# AICat_V1_3.net
KiCad netlist of a schematic drawn in Altium Designer
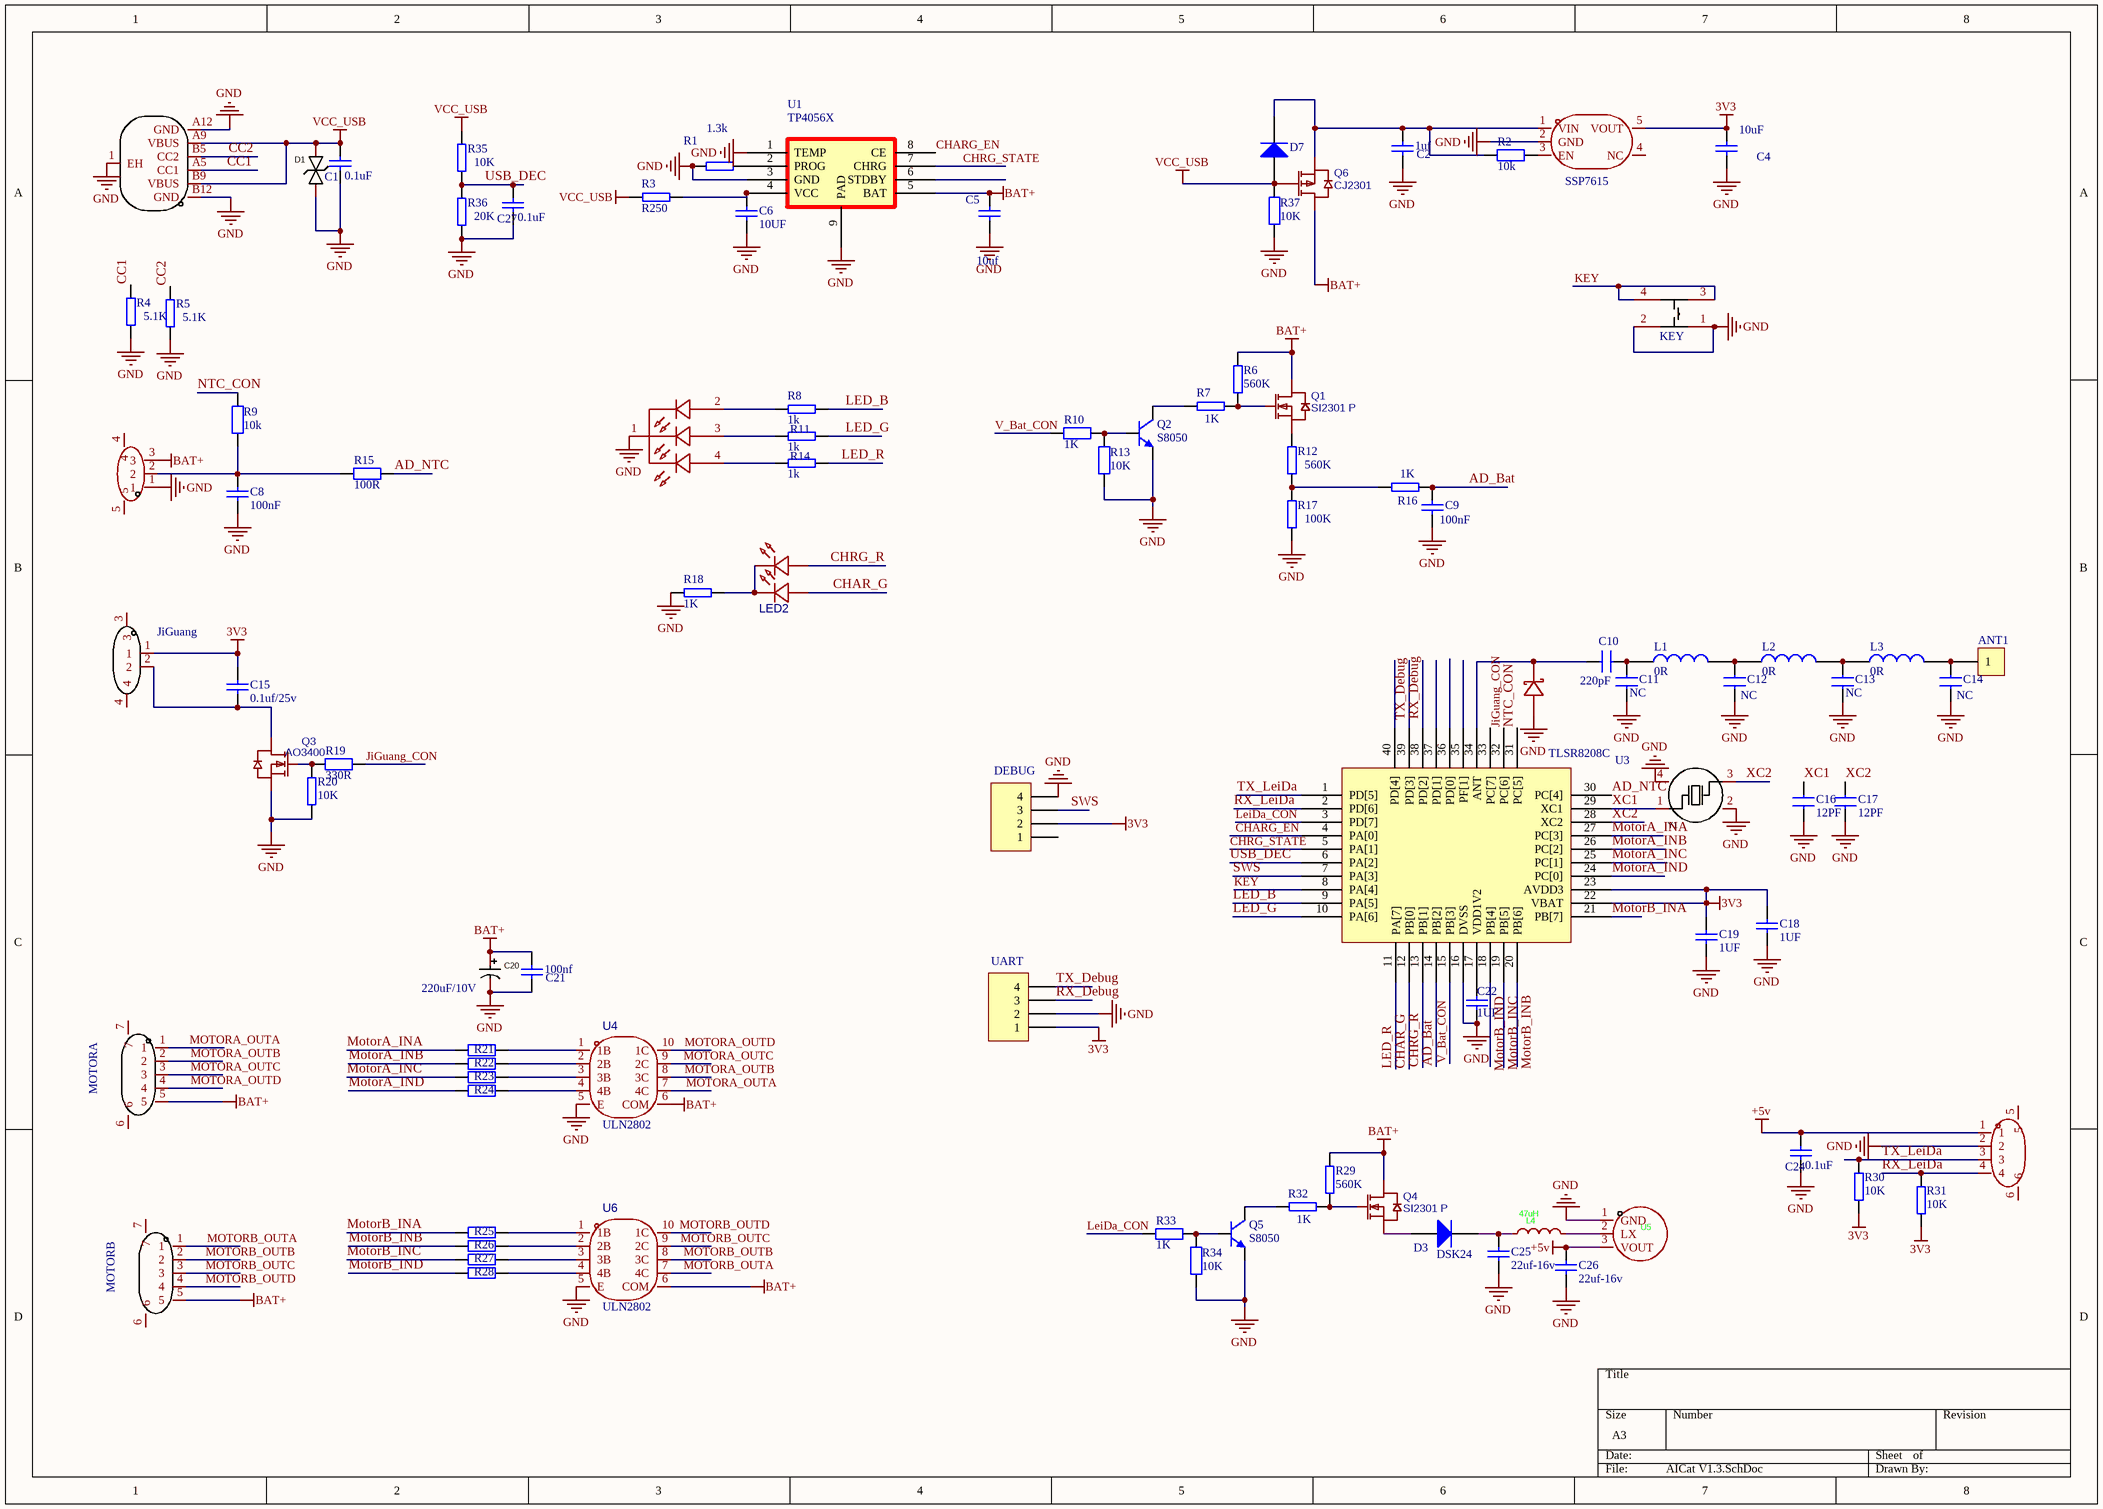
[diagram p0: AICat V1.3.SchDoc]

(export (version "E")
  (design (tool "Eeschema 10.0.6"))
  (components
    (comp (ref "ANT1")
      (value "~")
      (footprint "tp")
      (description "Connector")
      (libsource (lib "*") (part "CON1"))
    )
    (comp (ref "BAT1")
      (value "BX-PH2.0-3PWT")
      (footprint "HDR-TH_3P-P2.50_ZX-XH2.54-3PWZ")
      (libsource (lib "altium-import") (part "root_2_BX-PH2.0-3PWT_"))
    )
    (comp (ref "C1")
      (value "0.1uF")
      (footprint "0603_C")
      (description "Capacitor")
      (fields (field (name "PUBLISHER") "Altium Limited"))
      (libsource (lib "*") (part "Cap"))
    )
    (comp (ref "C2")
      (value "1uf")
      (footprint "0603_C")
      (description "无极电容")
      (libsource (lib "电容电阻电感保险") (part "Cap1"))
    )
    (comp (ref "C4")
      (value "10uF")
      (footprint "0603_C")
      (description "Capacitor")
      (fields (field (name "PUBLISHER") "Altium Limited"))
      (libsource (lib "*") (part "Cap"))
    )
    (comp (ref "C5")
      (value "10uf")
      (footprint "0603_C")
      (description "Capacitor")
      (fields (field (name "PUBLISHER") "Altium Limited"))
      (libsource (lib "*") (part "Cap"))
    )
    (comp (ref "C6") (value "10UF") (footprint "0603_c") (libsource (lib "DIY") (part "CAP")))
    (comp (ref "C8") (value "100nF") (footprint "0603_C") (libsource (lib "DIY") (part "CAP")))
    (comp (ref "C9") (value "100nF") (footprint "0603_C") (libsource (lib "DIY") (part "CAP")))
    (comp (ref "C10")
      (value "220pF")
      (footprint "0402_c")
      (description "Capacitor")
      (libsource (lib "*") (part "CAP"))
    )
    (comp (ref "C11")
      (value "NC")
      (footprint "0402_C")
      (description "Capacitor")
      (libsource (lib "*") (part "CAP"))
    )
    (comp (ref "C12")
      (value "NC")
      (footprint "0402_C")
      (description "Capacitor")
      (libsource (lib "*") (part "CAP"))
    )
    (comp (ref "C13")
      (value "NC")
      (footprint "0402_C")
      (description "Capacitor")
      (libsource (lib "*") (part "CAP"))
    )
    (comp (ref "C14")
      (value "NC")
      (footprint "0402_C")
      (description "Capacitor")
      (libsource (lib "*") (part "CAP"))
    )
    (comp (ref "C15")
      (value "0.1uf/25v")
      (footprint "0603_C")
      (description "Capacitor")
      (fields (field (name "PUBLISHER") "Altium Limited"))
      (libsource (lib "*") (part "Cap"))
    )
    (comp (ref "C16")
      (value "12PF")
      (footprint "0603_c")
      (description "Capacitor")
      (libsource (lib "*") (part "CAP"))
    )
    (comp (ref "C17")
      (value "12PF")
      (footprint "0603_c")
      (description "Capacitor")
      (libsource (lib "*") (part "CAP"))
    )
    (comp (ref "C18") (value "1UF") (footprint "0603_c") (libsource (lib "DIY") (part "CAP")))
    (comp (ref "C19") (value "1UF") (footprint "0603_c") (libsource (lib "DIY") (part "CAP")))
    (comp (ref "C20")
      (value "220uF/10V")
      (footprint "SMD 6.3*5.4 电解")
      (fields (field (name "MANUFACTURER PART") "RVT1A221M0605"))
      (libsource (lib "altium-import") (part "root_0_RVT1A221M0605_C72494_"))
    )
    (comp (ref "C21")
      (value "100nf")
      (footprint "0603_C")
      (description "无极电容")
      (libsource (lib "电容电阻电感保险") (part "Cap1"))
    )
    (comp (ref "C22") (value "1UF") (footprint "0603_c") (libsource (lib "DIY") (part "CAP")))
    (comp (ref "C24")
      (value "0.1uF")
      (footprint "0603_C")
      (description "Capacitor")
      (fields (field (name "PUBLISHER") "Altium Limited"))
      (libsource (lib "*") (part "Cap"))
    )
    (comp (ref "C25")
      (value "22uf-16v")
      (footprint "0805_c")
      (description "无极电容")
      (libsource (lib "电容电阻电感保险") (part "Cap1"))
    )
    (comp (ref "C26")
      (value "22uf-16v")
      (footprint "0805_c")
      (description "无极电容")
      (libsource (lib "电容电阻电感保险") (part "Cap1"))
    )
    (comp (ref "C27")
      (value "0.1uF")
      (footprint "0603_C")
      (description "Capacitor")
      (fields (field (name "PUBLISHER") "Altium Limited"))
      (libsource (lib "*") (part "Cap"))
    )
    (comp (ref "CN1")
      (value "JiGuang")
      (footprint "CONN-SMD_2P-P1.25-LT")
      (fields (field (name "MANUFACTURER PART") "HC-1.25-2PLT"))
      (libsource (lib "altium-import") (part "root_0_mirrored_HC-1.25-2PLT_"))
    )
    (comp (ref "CN2")
      (value "HC-1.25-4PLT")
      (footprint "CONN-SMD_4P-P1.25_LT")
      (libsource (lib "altium-import") (part "root_0_HC-1.25-4PLT_"))
    )
    (comp (ref "D1")
      (value "SMF5.0CA_C726939")
      (footprint "SOD-123 双向")
      (fields (field (name "MANUFACTURER PART") "SMF5.0CA"))
      (libsource (lib "altium-import") (part "root_1_SMF5.0CA_C726939_"))
    )
    (comp (ref "D2")
      (value "SE6V3LHN102T 6.3v单向")
      (footprint "0402-D")
      (libsource (lib "altium-import") (part "root_3_TPNSR05F20NXT5G_"))
    )
    (comp (ref "D3")
      (value "DSK24")
      (footprint "SOD-123FL")
      (description "High Conductance Fast Diode")
      (fields (field (name "PUBLISHER") "Altium Limited"))
      (libsource (lib "Miscellaneous Devices") (part "Diode 1N4148"))
    )
    (comp (ref "D7")
      (value "~")
      (footprint "SOD-123FL")
      (description "High Conductance Fast Diode")
      (fields (field (name "PUBLISHER") "Altium Limited"))
      (libsource (lib "Miscellaneous Devices") (part "Diode 1N4148"))
    )
    (comp (ref "J1")
      (value "MOTORA")
      (footprint "CONN-SMD_1.25-5PLT")
      (fields (field (name "MANUFACTURER PART") "HC-1.25-5PLT"))
      (libsource (lib "altium-import") (part "root_0_mirrored_HC-1.25-5PLT_"))
    )
    (comp (ref "J2")
      (value "MOTORB")
      (footprint "CONN-SMD_1.25-5PLT")
      (fields (field (name "MANUFACTURER PART") "HC-1.25-5PLT"))
      (libsource (lib "altium-import") (part "root_0_mirrored_HC-1.25-5PLT_"))
    )
    (comp (ref "K1")
      (value "KEY")
      (footprint "KEY_SMD_4P")
      (fields (field (name "MANUFACTURER PART") "TS-1002S-05026C"))
      (libsource (lib "altium-import") (part "root_2_TS-1002S-05026C_"))
    )
    (comp (ref "L1") (value "0R") (footprint "0402_R") (libsource (lib "*") (part "INDUCTOR")))
    (comp (ref "L2") (value "0R") (footprint "0402_R") (libsource (lib "*") (part "INDUCTOR")))
    (comp (ref "L3") (value "0R") (footprint "0402_R") (libsource (lib "*") (part "INDUCTOR")))
    (comp (ref "L4")
      (value "47uH")
      (footprint "IND-SMD_L3.5-W3.0_CD31")
      (fields (field (name "MANUFACTURER PART") "CD31-470M 47UH"))
      (libsource (lib "altium-import") (part "root_0_CD31-470M 47UH_"))
    )
    (comp (ref "LED1")
      (value "XL-A3528RGBC-BM")
      (footprint "LED-ARRAY-SMD_4P-L3.2-W2.8-LS3.5-BL_XL-A3528RGBC-BM")
      (libsource (lib "altium-import") (part "root_2_XL-A3528RGBC-BM_"))
    )
    (comp (ref "LED2")
      (value "*")
      (footprint "LED-SMD_4P-L3.2-W1.6-TL_XL-3216SURUGC")
      (libsource (lib "altium-import") (part "root_0_TJ-S2012SW8TCGLC2R2G-A5_"))
    )
    (comp (ref "P1")
      (value "DEBUG")
      (footprint "SIP4-2.54")
      (description "Header, 4-Pin")
      (fields (field (name "PUBLISHER") "Altium Limited"))
      (libsource (lib "Miscellaneous Connectors") (part "Header 4"))
    )
    (comp (ref "P2")
      (value "UART")
      (footprint "SIP4-2.54")
      (description "Header, 4-Pin")
      (fields (field (name "PUBLISHER") "Altium Limited"))
      (libsource (lib "Miscellaneous Connectors") (part "Header 4"))
    )
    (comp (ref "Q1")
      (value "SI2301 P")
      (footprint "SOT-23")
      (fields
        (field (name "BOM_SUPPLIER PART") "C2890442")
        (field (name "BOM_MANUFACTURER PART") "JMTL3400A")
        (field (name "CONTRIBUTOR") "LCSC")
      )
      (libsource (lib "altium-import") (part "root_0_JMTL3400A_"))
    )
    (comp (ref "Q2")
      (value "S8050")
      (footprint "SOT-23(SOT-23-3)")
      (description "NPN三极管")
      (libsource (lib "二三极管mos可控硅") (part "NPN_sot23"))
    )
    (comp (ref "Q3")
      (value "AO3400")
      (footprint "SOT-23")
      (fields
        (field (name "BOM_SUPPLIER PART") "C2890442")
        (field (name "BOM_MANUFACTURER PART") "JMTL3400A")
        (field (name "CONTRIBUTOR") "LCSC")
      )
      (libsource (lib "altium-import") (part "root_0_mirrored_JMTL3400A_"))
    )
    (comp (ref "Q4")
      (value "SI2301 P")
      (footprint "SOT-23")
      (fields
        (field (name "BOM_SUPPLIER PART") "C2890442")
        (field (name "BOM_MANUFACTURER PART") "JMTL3400A")
        (field (name "CONTRIBUTOR") "LCSC")
      )
      (libsource (lib "altium-import") (part "root_0_JMTL3400A_"))
    )
    (comp (ref "Q5")
      (value "S8050")
      (footprint "SOT-23(SOT-23-3)")
      (description "NPN三极管")
      (libsource (lib "二三极管mos可控硅") (part "NPN_sot23"))
    )
    (comp (ref "Q6")
      (value "CJ2301")
      (footprint "SOT-23")
      (fields (field (name "BOM_MANUFACTURER PART") "CJ3401") (field (name "BOM_SUPPLIER PART") "C13799"))
      (libsource (lib "altium-import") (part "root_2_mirrored_CJ3401_"))
    )
    (comp (ref "R1") (value "1.3k") (footprint "0603_R") (libsource (lib "DIY") (part "RES")))
    (comp (ref "R2")
      (value "10k")
      (footprint "0603_R")
      (description "Resistor")
      (fields (field (name "PUBLISHER") "Altium Limited"))
      (libsource (lib "") (part "Res2_3"))
    )
    (comp (ref "R3") (value "R250") (footprint "1206_R") (libsource (lib "DIY") (part "RES")))
    (comp (ref "R4") (value "5.1K") (footprint "0603_R") (libsource (lib "DIY") (part "RES")))
    (comp (ref "R5") (value "5.1K") (footprint "0603_R") (libsource (lib "DIY") (part "RES")))
    (comp (ref "R6") (value "560K") (footprint "0603_R") (libsource (lib "*") (part "RES")))
    (comp (ref "R7") (value "1K") (footprint "0603_R") (libsource (lib "") (part "RES_1")))
    (comp (ref "R8") (value "1k") (footprint "0603_R") (libsource (lib "DIY") (part "RES")))
    (comp (ref "R9")
      (value "10k")
      (footprint "0603_R")
      (description "Resistor")
      (fields (field (name "PUBLISHER") "Altium Limited"))
      (libsource (lib "*") (part "Res2"))
    )
    (comp (ref "R10")
      (value "1K")
      (footprint "0603_r")
      (description "Resistor")
      (fields (field (name "PUBLISHER") "Altium Limited"))
      (libsource (lib "") (part "Res2_2"))
    )
    (comp (ref "R11") (value "1k") (footprint "0603_R") (libsource (lib "DIY") (part "RES")))
    (comp (ref "R12") (value "560K") (footprint "0603_R") (libsource (lib "DIY") (part "RES")))
    (comp (ref "R13")
      (value "10K")
      (footprint "0603_r")
      (description "Resistor")
      (fields (field (name "PUBLISHER") "Altium Limited"))
      (libsource (lib "") (part "Res2_3"))
    )
    (comp (ref "R14") (value "1k") (footprint "0603_R") (libsource (lib "DIY") (part "RES")))
    (comp (ref "R15")
      (value "100R")
      (footprint "0603_R")
      (description "Resistor")
      (fields (field (name "PUBLISHER") "Altium Limited"))
      (libsource (lib "") (part "Res2_4"))
    )
    (comp (ref "R16") (value "1K") (footprint "0603_R") (libsource (lib "DIY") (part "RES")))
    (comp (ref "R17") (value "100K") (footprint "0603_R") (libsource (lib "DIY") (part "RES")))
    (comp (ref "R18") (value "1K") (footprint "0603_R") (libsource (lib "DIY") (part "RES")))
    (comp (ref "R19")
      (value "330R")
      (footprint "0603_R")
      (description "Resistor")
      (fields (field (name "PUBLISHER") "Altium Limited"))
      (libsource (lib "*") (part "Res2"))
    )
    (comp (ref "R20") (value "10K") (footprint "0603_R") (libsource (lib "DIY") (part "RES")))
    (comp (ref "R21")
      (value "330R")
      (footprint "0603_R")
      (description "Resistor")
      (fields (field (name "PUBLISHER") "Altium Limited"))
      (libsource (lib "") (part "Res2_1"))
    )
    (comp (ref "R22")
      (value "330R")
      (footprint "0603_R")
      (description "Resistor")
      (fields (field (name "PUBLISHER") "Altium Limited"))
      (libsource (lib "") (part "Res2_1"))
    )
    (comp (ref "R23")
      (value "330R")
      (footprint "0603_R")
      (description "Resistor")
      (fields (field (name "PUBLISHER") "Altium Limited"))
      (libsource (lib "") (part "Res2_1"))
    )
    (comp (ref "R24")
      (value "330R")
      (footprint "0603_R")
      (description "Resistor")
      (fields (field (name "PUBLISHER") "Altium Limited"))
      (libsource (lib "") (part "Res2_1"))
    )
    (comp (ref "R25")
      (value "330R")
      (footprint "0603_R")
      (description "Resistor")
      (fields (field (name "PUBLISHER") "Altium Limited"))
      (libsource (lib "") (part "Res2_1"))
    )
    (comp (ref "R26")
      (value "330R")
      (footprint "0603_R")
      (description "Resistor")
      (fields (field (name "PUBLISHER") "Altium Limited"))
      (libsource (lib "") (part "Res2_1"))
    )
    (comp (ref "R27")
      (value "330R")
      (footprint "0603_R")
      (description "Resistor")
      (fields (field (name "PUBLISHER") "Altium Limited"))
      (libsource (lib "") (part "Res2_1"))
    )
    (comp (ref "R28")
      (value "330R")
      (footprint "0603_R")
      (description "Resistor")
      (fields (field (name "PUBLISHER") "Altium Limited"))
      (libsource (lib "") (part "Res2_1"))
    )
    (comp (ref "R29") (value "560K") (footprint "0603_R") (libsource (lib "*") (part "RES")))
    (comp (ref "R30") (value "10K") (footprint "0603_R") (libsource (lib "*") (part "RES")))
    (comp (ref "R31") (value "10K") (footprint "0603_R") (libsource (lib "*") (part "RES")))
    (comp (ref "R32") (value "1K") (footprint "0603_R") (libsource (lib "") (part "RES_1")))
    (comp (ref "R33")
      (value "1K")
      (footprint "0603_r")
      (description "Resistor")
      (fields (field (name "PUBLISHER") "Altium Limited"))
      (libsource (lib "") (part "Res2_2"))
    )
    (comp (ref "R34")
      (value "10K")
      (footprint "0603_r")
      (description "Resistor")
      (fields (field (name "PUBLISHER") "Altium Limited"))
      (libsource (lib "") (part "Res2_3"))
    )
    (comp (ref "R35") (value "10K") (footprint "0603_R") (libsource (lib "DIY") (part "RES")))
    (comp (ref "R36") (value "20K") (footprint "0603_R") (libsource (lib "DIY") (part "RES")))
    (comp (ref "R37")
      (value "10K")
      (footprint "0603_R")
      (description "Resistor")
      (fields (field (name "PUBLISHER") "Altium Limited"))
      (libsource (lib "*") (part "Res2"))
    )
    (comp (ref "U1")
      (value "TP4056X")
      (footprint "SOP8-9")
      (description "TP4056")
      (libsource (lib "芯片") (part "TP4056"))
    )
    (comp (ref "U2")
      (value "SSP7615")
      (footprint "SOT-23-5")
      (libsource (lib "altium-import") (part "root_0_SSP7615-33M5R_"))
    )
    (comp (ref "U3")
      (value "TLSR8208C")
      (footprint "QFN-40_L5.0-W5.0-P0.40-BL-EP3.7")
      (libsource (lib "MyLib") (part "TLSR8208C"))
    )
    (comp (ref "U4")
      (value "ULN2802")
      (footprint "ESSOP-10")
      (libsource (lib "altium-import") (part "root_0_ULN2802_C2828555_"))
    )
    (comp (ref "U5")
      (value "HE9116A50NR")
      (footprint "SOT-23")
      (libsource (lib "altium-import") (part "root_0_HE9116A50NR_"))
    )
    (comp (ref "U6")
      (value "ULN2802")
      (footprint "ESSOP-10")
      (libsource (lib "altium-import") (part "root_0_ULN2802_C2828555_"))
    )
    (comp (ref "USB1")
      (value "TYPE-C 6P")
      (footprint "TPYE-C-6")
      (fields (field (name "MANUFACTURER PART") "TYPE-C 6P LTH6.5"))
      (libsource (lib "altium-import") (part "root_2_TYPE-C 6P LTH6.5_"))
    )
    (comp (ref "Y1")
      (value "24MHz +-20PPM")
      (footprint "CRYSTAL-SMD_4P-L3.2-W2.5")
      (fields (field (name "MANUFACTURER PART") "TAXM13.56M4RLBCCT2T"))
      (libsource (lib "altium-import") (part "root_0_TAXM13.56M4RLBCCT2T_"))
    )
  )
  (nets
    (net (code "1") (name "+5v") (class "Default")
      (node (ref "C24") (pin "2") (pinfunction "2_2") (pintype "passive"))
      (node (ref "C26") (pin "1") (pinfunction "1_1") (pintype "passive"))
      (node (ref "CN2") (pin "1") (pinfunction "1_1") (pintype "passive"))
      (node (ref "U5") (pin "3") (pinfunction "VOUT_3") (pintype "passive"))
    )
    (net (code "2") (name "/AD_Bat") (class "Default")
      (node (ref "C9") (pin "2") (pintype "passive"))
      (node (ref "R16") (pin "1") (pinfunction "1_1") (pintype "passive"))
      (node (ref "U3") (pin "14") (pinfunction "PB[2]_14") (pintype "passive"))
    )
    (net (code "3") (name "/AD_NTC") (class "Default")
      (node (ref "R15") (pin "1") (pinfunction "1_1") (pintype "passive"))
      (node (ref "U3") (pin "30") (pinfunction "PC[4]_30") (pintype "passive"))
    )
    (net (code "4") (name "/CC1") (class "Default")
      (node (ref "R4") (pin "1") (pinfunction "1_1") (pintype "passive"))
      (node (ref "USB1") (pin "A5") (pinfunction "CC1_A5") (pintype "passive"))
    )
    (net (code "5") (name "/CC2") (class "Default")
      (node (ref "R5") (pin "1") (pinfunction "1_1") (pintype "passive"))
      (node (ref "USB1") (pin "B5") (pinfunction "CC2_B5") (pintype "passive"))
    )
    (net (code "6") (name "/CHARG_EN") (class "Default")
      (node (ref "U1") (pin "8") (pinfunction "CE_8") (pintype "passive"))
      (node (ref "U3") (pin "4") (pinfunction "PA[0]_4") (pintype "passive"))
    )
    (net (code "7") (name "/CHAR_G") (class "Default")
      (node (ref "LED2") (pin "3") (pinfunction "A_3") (pintype "passive"))
      (node (ref "U3") (pin "12") (pinfunction "PB[0]_12") (pintype "passive"))
    )
    (net (code "8") (name "/CHRG_R") (class "Default")
      (node (ref "LED2") (pin "1") (pinfunction "A_1") (pintype "passive"))
      (node (ref "U3") (pin "13") (pinfunction "PB[1]_13") (pintype "passive"))
    )
    (net (code "9") (name "/CHRG_STATE") (class "Default")
      (node (ref "U1") (pin "7") (pinfunction "CHRG_7") (pintype "passive"))
      (node (ref "U3") (pin "5") (pinfunction "PA[1]_5") (pintype "passive"))
    )
    (net (code "10") (name "/JiGuang_CON") (class "Default")
      (node (ref "R19") (pin "2") (pinfunction "2_2") (pintype "passive"))
      (node (ref "U3") (pin "32") (pinfunction "PC[6]_32") (pintype "passive"))
    )
    (net (code "11") (name "/KEY") (class "Default")
      (node (ref "K1") (pin "3") (pinfunction "3_3") (pintype "passive"))
      (node (ref "K1") (pin "4") (pinfunction "4_4") (pintype "passive"))
      (node (ref "U3") (pin "8") (pinfunction "PA[4]_8") (pintype "passive"))
    )
    (net (code "12") (name "/LED_B") (class "Default")
      (node (ref "R8") (pin "2") (pinfunction "2_2") (pintype "passive"))
      (node (ref "U3") (pin "9") (pinfunction "PA[5]_9") (pintype "passive"))
    )
    (net (code "13") (name "/LED_G") (class "Default")
      (node (ref "R11") (pin "2") (pinfunction "2_2") (pintype "passive"))
      (node (ref "U3") (pin "10") (pinfunction "PA[6]_10") (pintype "passive"))
    )
    (net (code "14") (name "/LED_R") (class "Default")
      (node (ref "R14") (pin "2") (pinfunction "2_2") (pintype "passive"))
      (node (ref "U3") (pin "11") (pinfunction "PA[7]_11") (pintype "passive"))
    )
    (net (code "15") (name "/LeiDa_CON") (class "Default")
      (node (ref "R33") (pin "2") (pinfunction "2_2") (pintype "passive"))
      (node (ref "U3") (pin "3") (pinfunction "PD[7]_3") (pintype "passive"))
    )
    (net (code "16") (name "/MOTORA_OUTA") (class "Default")
      (node (ref "J1") (pin "1") (pinfunction "1_1") (pintype "passive"))
      (node (ref "U4") (pin "7") (pinfunction "4C_7") (pintype "passive"))
    )
    (net (code "17") (name "/MOTORA_OUTB") (class "Default")
      (node (ref "J1") (pin "2") (pinfunction "2_2") (pintype "passive"))
      (node (ref "U4") (pin "8") (pinfunction "3C_8") (pintype "passive"))
    )
    (net (code "18") (name "/MOTORA_OUTC") (class "Default")
      (node (ref "J1") (pin "3") (pinfunction "3_3") (pintype "passive"))
      (node (ref "U4") (pin "9") (pinfunction "2C_9") (pintype "passive"))
    )
    (net (code "19") (name "/MOTORA_OUTD") (class "Default")
      (node (ref "J1") (pin "4") (pinfunction "4_4") (pintype "passive"))
      (node (ref "U4") (pin "10") (pinfunction "1C_10") (pintype "passive"))
    )
    (net (code "20") (name "/MOTORB_OUTA") (class "Default")
      (node (ref "J2") (pin "1") (pinfunction "1_1") (pintype "passive"))
      (node (ref "U6") (pin "7") (pinfunction "4C_7") (pintype "passive"))
    )
    (net (code "21") (name "/MOTORB_OUTB") (class "Default")
      (node (ref "J2") (pin "2") (pinfunction "2_2") (pintype "passive"))
      (node (ref "U6") (pin "8") (pinfunction "3C_8") (pintype "passive"))
    )
    (net (code "22") (name "/MOTORB_OUTC") (class "Default")
      (node (ref "J2") (pin "3") (pinfunction "3_3") (pintype "passive"))
      (node (ref "U6") (pin "9") (pinfunction "2C_9") (pintype "passive"))
    )
    (net (code "23") (name "/MOTORB_OUTD") (class "Default")
      (node (ref "J2") (pin "4") (pinfunction "4_4") (pintype "passive"))
      (node (ref "U6") (pin "10") (pinfunction "1C_10") (pintype "passive"))
    )
    (net (code "24") (name "/MotorA_INA") (class "Default")
      (node (ref "R21") (pin "2") (pinfunction "2_2") (pintype "passive"))
      (node (ref "U3") (pin "27") (pinfunction "PC[3]_27") (pintype "passive"))
    )
    (net (code "25") (name "/MotorA_INB") (class "Default")
      (node (ref "R22") (pin "2") (pinfunction "2_2") (pintype "passive"))
      (node (ref "U3") (pin "26") (pinfunction "PC[2]_26") (pintype "passive"))
    )
    (net (code "26") (name "/MotorA_INC") (class "Default")
      (node (ref "R23") (pin "2") (pinfunction "2_2") (pintype "passive"))
      (node (ref "U3") (pin "25") (pinfunction "PC[1]_25") (pintype "passive"))
    )
    (net (code "27") (name "/MotorA_IND") (class "Default")
      (node (ref "R24") (pin "2") (pinfunction "2_2") (pintype "passive"))
      (node (ref "U3") (pin "24") (pinfunction "PC[0]_24") (pintype "passive"))
    )
    (net (code "28") (name "/MotorB_INA") (class "Default")
      (node (ref "R25") (pin "2") (pinfunction "2_2") (pintype "passive"))
      (node (ref "U3") (pin "21") (pinfunction "PB[7]_21") (pintype "passive"))
    )
    (net (code "29") (name "/MotorB_INB") (class "Default")
      (node (ref "R26") (pin "2") (pinfunction "2_2") (pintype "passive"))
      (node (ref "U3") (pin "20") (pinfunction "PB[6]_20") (pintype "passive"))
    )
    (net (code "30") (name "/MotorB_INC") (class "Default")
      (node (ref "R27") (pin "2") (pinfunction "2_2") (pintype "passive"))
      (node (ref "U3") (pin "19") (pinfunction "PB[5]_19") (pintype "passive"))
    )
    (net (code "31") (name "/MotorB_IND") (class "Default")
      (node (ref "R28") (pin "2") (pinfunction "2_2") (pintype "passive"))
      (node (ref "U3") (pin "18") (pinfunction "PB[4]_18") (pintype "passive"))
    )
    (net (code "32") (name "/NTC_CON") (class "Default")
      (node (ref "R9") (pin "2") (pinfunction "2_2") (pintype "passive"))
      (node (ref "U3") (pin "31") (pinfunction "PC[5]_31") (pintype "passive"))
    )
    (net (code "33") (name "/RX_Debug") (class "Default")
      (node (ref "P2") (pin "3") (pinfunction "3_3") (pintype "passive"))
      (node (ref "U3") (pin "38") (pinfunction "PD[2]_38") (pintype "passive"))
    )
    (net (code "34") (name "/RX_LeiDa") (class "Default")
      (node (ref "CN2") (pin "4") (pinfunction "4_4") (pintype "passive"))
      (node (ref "R31") (pin "1") (pintype "passive"))
      (node (ref "U3") (pin "2") (pinfunction "PD[6]_2") (pintype "passive"))
    )
    (net (code "35") (name "/SWS") (class "Default")
      (node (ref "P1") (pin "3") (pinfunction "3_3") (pintype "passive"))
      (node (ref "U3") (pin "7") (pinfunction "PA[3]_7") (pintype "passive"))
    )
    (net (code "36") (name "/TX_Debug") (class "Default")
      (node (ref "P2") (pin "4") (pinfunction "4_4") (pintype "passive"))
      (node (ref "U3") (pin "39") (pinfunction "PD[3]_39") (pintype "passive"))
    )
    (net (code "37") (name "/TX_LeiDa") (class "Default")
      (node (ref "CN2") (pin "3") (pinfunction "3_3") (pintype "passive"))
      (node (ref "R30") (pin "1") (pintype "passive"))
      (node (ref "U3") (pin "1") (pinfunction "PD[5]_1") (pintype "passive"))
    )
    (net (code "38") (name "/USB_DEC") (class "Default")
      (node (ref "C27") (pin "2") (pinfunction "2_2") (pintype "passive"))
      (node (ref "R35") (pin "2") (pinfunction "2_2") (pintype "passive"))
      (node (ref "R36") (pin "1") (pinfunction "1_1") (pintype "passive"))
      (node (ref "U3") (pin "6") (pinfunction "PA[2]_6") (pintype "passive"))
    )
    (net (code "39") (name "/V_Bat_CON") (class "Default")
      (node (ref "R10") (pin "2") (pinfunction "2_2") (pintype "passive"))
      (node (ref "U3") (pin "15") (pinfunction "PB[3]_15") (pintype "passive"))
    )
    (net (code "40") (name "/XC1") (class "Default")
      (node (ref "C16") (pin "2") (pinfunction "2_2") (pintype "passive"))
      (node (ref "U3") (pin "29") (pinfunction "XC1_29") (pintype "passive"))
      (node (ref "Y1") (pin "1") (pinfunction "OSC1_1") (pintype "passive"))
    )
    (net (code "41") (name "/XC2") (class "Default")
      (node (ref "C17") (pin "2") (pinfunction "2_2") (pintype "passive"))
      (node (ref "U3") (pin "28") (pinfunction "XC2_28") (pintype "passive"))
      (node (ref "Y1") (pin "3") (pinfunction "OSC2_3") (pintype "passive"))
    )
    (net (code "42") (name "3V3") (class "Default")
      (node (ref "C15") (pin "2") (pinfunction "2_2") (pintype "passive"))
      (node (ref "C18") (pin "1") (pintype "passive"))
      (node (ref "C19") (pin "1") (pintype "passive"))
      (node (ref "C4") (pin "2") (pinfunction "2_2") (pintype "passive"))
      (node (ref "CN1") (pin "1") (pinfunction "1_1") (pintype "passive"))
      (node (ref "P1") (pin "2") (pinfunction "2_2") (pintype "passive"))
      (node (ref "P2") (pin "1") (pinfunction "1_1") (pintype "passive"))
      (node (ref "R30") (pin "2") (pintype "passive"))
      (node (ref "R31") (pin "2") (pintype "passive"))
      (node (ref "U2") (pin "5") (pinfunction "VOUT_5") (pintype "passive"))
      (node (ref "U3") (pin "22") (pinfunction "VBAT_22") (pintype "passive"))
      (node (ref "U3") (pin "23") (pinfunction "AVDD3_23") (pintype "passive"))
    )
    (net (code "43") (name "BAT+") (class "Default")
      (node (ref "BAT1") (pin "3") (pinfunction "3_3") (pintype "passive"))
      (node (ref "C20") (pin "1") (pinfunction "1_1") (pintype "passive"))
      (node (ref "C21") (pin "2") (pinfunction "2_2") (pintype "passive"))
      (node (ref "C5") (pin "1") (pinfunction "1_1") (pintype "passive"))
      (node (ref "J1") (pin "5") (pinfunction "5_5") (pintype "passive"))
      (node (ref "J2") (pin "5") (pinfunction "5_5") (pintype "passive"))
      (node (ref "Q1") (pin "2") (pinfunction "D_2") (pintype "passive"))
      (node (ref "Q4") (pin "2") (pinfunction "D_2") (pintype "passive"))
      (node (ref "Q6") (pin "3") (pinfunction "D_3") (pintype "passive"))
      (node (ref "R29") (pin "1") (pintype "passive"))
      (node (ref "R6") (pin "1") (pintype "passive"))
      (node (ref "U1") (pin "5") (pinfunction "BAT_5") (pintype "passive"))
      (node (ref "U4") (pin "6") (pinfunction "COM_6") (pintype "passive"))
      (node (ref "U6") (pin "6") (pinfunction "COM_6") (pintype "passive"))
    )
    (net (code "44") (name "GND") (class "Default")
      (node (ref "BAT1") (pin "1") (pinfunction "1_1") (pintype "passive"))
      (node (ref "C1") (pin "1") (pinfunction "1_1") (pintype "passive"))
      (node (ref "C11") (pin "1") (pinfunction "1_1") (pintype "passive"))
      (node (ref "C12") (pin "1") (pinfunction "1_1") (pintype "passive"))
      (node (ref "C13") (pin "1") (pinfunction "1_1") (pintype "passive"))
      (node (ref "C14") (pin "1") (pinfunction "1_1") (pintype "passive"))
      (node (ref "C16") (pin "1") (pinfunction "1_1") (pintype "passive"))
      (node (ref "C17") (pin "1") (pinfunction "1_1") (pintype "passive"))
      (node (ref "C18") (pin "2") (pintype "passive"))
      (node (ref "C19") (pin "2") (pintype "passive"))
      (node (ref "C2") (pin "1") (pinfunction "1_1") (pintype "passive"))
      (node (ref "C20") (pin "2") (pinfunction "2_2") (pintype "passive"))
      (node (ref "C21") (pin "1") (pinfunction "1_1") (pintype "passive"))
      (node (ref "C22") (pin "1") (pintype "passive"))
      (node (ref "C24") (pin "1") (pinfunction "1_1") (pintype "passive"))
      (node (ref "C25") (pin "2") (pinfunction "2_2") (pintype "passive"))
      (node (ref "C26") (pin "2") (pinfunction "2_2") (pintype "passive"))
      (node (ref "C27") (pin "1") (pinfunction "1_1") (pintype "passive"))
      (node (ref "C4") (pin "1") (pinfunction "1_1") (pintype "passive"))
      (node (ref "C5") (pin "2") (pinfunction "2_2") (pintype "passive"))
      (node (ref "C6") (pin "1") (pintype "passive"))
      (node (ref "C8") (pin "2") (pintype "passive"))
      (node (ref "C9") (pin "1") (pintype "passive"))
      (node (ref "CN2") (pin "2") (pinfunction "2_2") (pintype "passive"))
      (node (ref "D1") (pin "1") (pinfunction "1_1") (pintype "passive"))
      (node (ref "D2") (pin "2") (pinfunction "A_2") (pintype "passive"))
      (node (ref "K1") (pin "1") (pinfunction "1_1") (pintype "passive"))
      (node (ref "K1") (pin "2") (pinfunction "2_2") (pintype "passive"))
      (node (ref "LED1") (pin "1") (pinfunction "1_1") (pintype "passive"))
      (node (ref "P1") (pin "4") (pinfunction "4_4") (pintype "passive"))
      (node (ref "P2") (pin "2") (pinfunction "2_2") (pintype "passive"))
      (node (ref "Q2") (pin "2") (pinfunction "E_2") (pintype "passive"))
      (node (ref "Q3") (pin "2") (pinfunction "S_2") (pintype "passive"))
      (node (ref "Q5") (pin "2") (pinfunction "E_2") (pintype "passive"))
      (node (ref "R1") (pin "1") (pinfunction "1_1") (pintype "passive"))
      (node (ref "R13") (pin "1") (pinfunction "1_1") (pintype "passive"))
      (node (ref "R17") (pin "2") (pinfunction "2_2") (pintype "passive"))
      (node (ref "R18") (pin "1") (pinfunction "1_1") (pintype "passive"))
      (node (ref "R20") (pin "1") (pinfunction "1_1") (pintype "passive"))
      (node (ref "R34") (pin "1") (pinfunction "1_1") (pintype "passive"))
      (node (ref "R36") (pin "2") (pinfunction "2_2") (pintype "passive"))
      (node (ref "R37") (pin "1") (pinfunction "1_1") (pintype "passive"))
      (node (ref "R4") (pin "2") (pinfunction "2_2") (pintype "passive"))
      (node (ref "R5") (pin "2") (pinfunction "2_2") (pintype "passive"))
      (node (ref "U1") (pin "1") (pinfunction "TEMP_1") (pintype "passive"))
      (node (ref "U1") (pin "3") (pinfunction "GND_3") (pintype "passive"))
      (node (ref "U1") (pin "9") (pinfunction "PAD_9") (pintype "passive"))
      (node (ref "U2") (pin "2") (pinfunction "GND_2") (pintype "passive"))
      (node (ref "U3") (pin "16") (pinfunction "DVSS_16") (pintype "passive"))
      (node (ref "U4") (pin "5") (pinfunction "E_5") (pintype "passive"))
      (node (ref "U5") (pin "1") (pinfunction "GND_1") (pintype "passive"))
      (node (ref "U6") (pin "5") (pinfunction "E_5") (pintype "passive"))
      (node (ref "USB1") (pin "1") (pinfunction "EH_1") (pintype "passive"))
      (node (ref "USB1") (pin "A12") (pinfunction "GND_A12") (pintype "passive"))
      (node (ref "USB1") (pin "B12") (pinfunction "GND_B12") (pintype "passive"))
      (node (ref "Y1") (pin "2") (pinfunction "GND_2") (pintype "passive"))
      (node (ref "Y1") (pin "4") (pinfunction "GND_4") (pintype "passive"))
    )
    (net (code "45") (name "Net-(ANT1-Pad1)") (class "Default")
      (node (ref "ANT1") (pin "1") (pinfunction "1_1") (pintype "passive"))
      (node (ref "C14") (pin "2") (pinfunction "2_2") (pintype "passive"))
      (node (ref "L3") (pin "2") (pinfunction "2_2") (pintype "passive"))
    )
    (net (code "46") (name "Net-(BAT1-Pad2)") (class "Default")
      (node (ref "BAT1") (pin "2") (pinfunction "2_2") (pintype "passive"))
      (node (ref "C8") (pin "1") (pintype "passive"))
      (node (ref "R15") (pin "2") (pinfunction "2_2") (pintype "passive"))
      (node (ref "R9") (pin "1") (pinfunction "1_1") (pintype "passive"))
    )
    (net (code "47") (name "Net-(C10-Pad2)") (class "Default")
      (node (ref "C10") (pin "2") (pinfunction "2_2") (pintype "passive"))
      (node (ref "C11") (pin "2") (pinfunction "2_2") (pintype "passive"))
      (node (ref "L1") (pin "1") (pinfunction "1_1") (pintype "passive"))
    )
    (net (code "48") (name "Net-(C12-Pad2)") (class "Default")
      (node (ref "C12") (pin "2") (pinfunction "2_2") (pintype "passive"))
      (node (ref "L1") (pin "2") (pinfunction "2_2") (pintype "passive"))
      (node (ref "L2") (pin "1") (pinfunction "1_1") (pintype "passive"))
    )
    (net (code "49") (name "Net-(C13-Pad2)") (class "Default")
      (node (ref "C13") (pin "2") (pinfunction "2_2") (pintype "passive"))
      (node (ref "L2") (pin "2") (pinfunction "2_2") (pintype "passive"))
      (node (ref "L3") (pin "1") (pinfunction "1_1") (pintype "passive"))
    )
    (net (code "50") (name "Net-(D2-C)") (class "Default")
      (node (ref "C10") (pin "1") (pinfunction "1_1") (pintype "passive"))
      (node (ref "D2") (pin "1") (pinfunction "C_1") (pintype "passive"))
      (node (ref "U3") (pin "34") (pinfunction "ANT_34") (pintype "passive"))
    )
    (net (code "51") (name "Net-(D3-A)") (class "Default")
      (node (ref "D3") (pin "1") (pinfunction "A_1") (pintype "passive"))
      (node (ref "Q4") (pin "3") (pinfunction "S_3") (pintype "passive"))
    )
    (net (code "52") (name "Net-(D3-K)") (class "Default")
      (node (ref "C25") (pin "1") (pinfunction "1_1") (pintype "passive"))
      (node (ref "D3") (pin "2") (pinfunction "K_2") (pintype "passive"))
      (node (ref "L4") (pin "1") (pinfunction "1_1") (pintype "passive"))
    )
    (net (code "53") (name "Net-(D7-K)") (class "Default")
      (node (ref "C2") (pin "2") (pinfunction "2_2") (pintype "passive"))
      (node (ref "D7") (pin "2") (pinfunction "K_2") (pintype "passive"))
      (node (ref "Q6") (pin "2") (pinfunction "S_2") (pintype "passive"))
      (node (ref "R2") (pin "1") (pinfunction "1_1") (pintype "passive"))
      (node (ref "U2") (pin "1") (pinfunction "VIN_1") (pintype "passive"))
    )
    (net (code "54") (name "Net-(LED1-Pad2)") (class "Default")
      (node (ref "LED1") (pin "2") (pinfunction "2_2") (pintype "passive"))
      (node (ref "R8") (pin "1") (pinfunction "1_1") (pintype "passive"))
    )
    (net (code "55") (name "Net-(LED1-Pad3)") (class "Default")
      (node (ref "LED1") (pin "3") (pinfunction "3_3") (pintype "passive"))
      (node (ref "R11") (pin "1") (pinfunction "1_1") (pintype "passive"))
    )
    (net (code "56") (name "Net-(LED1-Pad4)") (class "Default")
      (node (ref "LED1") (pin "4") (pinfunction "4_4") (pintype "passive"))
      (node (ref "R14") (pin "1") (pinfunction "1_1") (pintype "passive"))
    )
    (net (code "57") (name "Net-(LED2-K-Pad2)") (class "Default")
      (node (ref "LED2") (pin "2") (pinfunction "K_2") (pintype "passive"))
      (node (ref "LED2") (pin "4") (pinfunction "K_4") (pintype "passive"))
      (node (ref "R18") (pin "2") (pinfunction "2_2") (pintype "passive"))
    )
    (net (code "58") (name "Net-(Q1-G)") (class "Default")
      (node (ref "Q1") (pin "1") (pinfunction "G_1") (pintype "passive"))
      (node (ref "R6") (pin "2") (pintype "passive"))
      (node (ref "R7") (pin "1") (pintype "passive"))
    )
    (net (code "59") (name "Net-(Q1-S)") (class "Default")
      (node (ref "Q1") (pin "3") (pinfunction "S_3") (pintype "passive"))
      (node (ref "R12") (pin "1") (pinfunction "1_1") (pintype "passive"))
    )
    (net (code "60") (name "Net-(Q2-B)") (class "Default")
      (node (ref "Q2") (pin "1") (pinfunction "B_1") (pintype "passive"))
      (node (ref "R10") (pin "1") (pinfunction "1_1") (pintype "passive"))
      (node (ref "R13") (pin "2") (pinfunction "2_2") (pintype "passive"))
    )
    (net (code "61") (name "Net-(Q2-C)") (class "Default")
      (node (ref "Q2") (pin "3") (pinfunction "C_3") (pintype "passive"))
      (node (ref "R7") (pin "2") (pintype "passive"))
    )
    (net (code "62") (name "Net-(Q3-D)") (class "Default")
      (node (ref "C15") (pin "1") (pinfunction "1_1") (pintype "passive"))
      (node (ref "CN1") (pin "2") (pinfunction "2_2") (pintype "passive"))
      (node (ref "Q3") (pin "3") (pinfunction "D_3") (pintype "passive"))
    )
    (net (code "63") (name "Net-(Q3-G)") (class "Default")
      (node (ref "Q3") (pin "1") (pinfunction "G_1") (pintype "passive"))
      (node (ref "R19") (pin "1") (pinfunction "1_1") (pintype "passive"))
      (node (ref "R20") (pin "2") (pinfunction "2_2") (pintype "passive"))
    )
    (net (code "64") (name "Net-(Q4-G)") (class "Default")
      (node (ref "Q4") (pin "1") (pinfunction "G_1") (pintype "passive"))
      (node (ref "R29") (pin "2") (pintype "passive"))
      (node (ref "R32") (pin "1") (pintype "passive"))
    )
    (net (code "65") (name "Net-(Q5-B)") (class "Default")
      (node (ref "Q5") (pin "1") (pinfunction "B_1") (pintype "passive"))
      (node (ref "R33") (pin "1") (pinfunction "1_1") (pintype "passive"))
      (node (ref "R34") (pin "2") (pinfunction "2_2") (pintype "passive"))
    )
    (net (code "66") (name "Net-(Q5-C)") (class "Default")
      (node (ref "Q5") (pin "3") (pinfunction "C_3") (pintype "passive"))
      (node (ref "R32") (pin "2") (pintype "passive"))
    )
    (net (code "67") (name "Net-(R12-Pad2)") (class "Default")
      (node (ref "R12") (pin "2") (pinfunction "2_2") (pintype "passive"))
      (node (ref "R16") (pin "2") (pinfunction "2_2") (pintype "passive"))
      (node (ref "R17") (pin "1") (pinfunction "1_1") (pintype "passive"))
    )
    (net (code "68") (name "Net-(U1-PROG)") (class "Default")
      (node (ref "R1") (pin "2") (pinfunction "2_2") (pintype "passive"))
      (node (ref "U1") (pin "2") (pinfunction "PROG_2") (pintype "passive"))
    )
    (net (code "69") (name "Net-(U1-VCC)") (class "Default")
      (node (ref "C6") (pin "2") (pintype "passive"))
      (node (ref "R3") (pin "1") (pinfunction "1_1") (pintype "passive"))
      (node (ref "U1") (pin "4") (pinfunction "VCC_4") (pintype "passive"))
    )
    (net (code "70") (name "Net-(U2-EN)") (class "Default")
      (node (ref "R2") (pin "2") (pinfunction "2_2") (pintype "passive"))
      (node (ref "U2") (pin "3") (pinfunction "EN_3") (pintype "passive"))
    )
    (net (code "71") (name "Net-(U3-VDD1V2)") (class "Default")
      (node (ref "C22") (pin "2") (pintype "passive"))
      (node (ref "U3") (pin "17") (pinfunction "VDD1V2_17") (pintype "passive"))
    )
    (net (code "72") (name "Net-(U4-1B)") (class "Default")
      (node (ref "R21") (pin "1") (pinfunction "1_1") (pintype "passive"))
      (node (ref "U4") (pin "1") (pinfunction "1B_1") (pintype "passive"))
    )
    (net (code "73") (name "Net-(U4-2B)") (class "Default")
      (node (ref "R22") (pin "1") (pinfunction "1_1") (pintype "passive"))
      (node (ref "U4") (pin "2") (pinfunction "2B_2") (pintype "passive"))
    )
    (net (code "74") (name "Net-(U4-3B)") (class "Default")
      (node (ref "R23") (pin "1") (pinfunction "1_1") (pintype "passive"))
      (node (ref "U4") (pin "3") (pinfunction "3B_3") (pintype "passive"))
    )
    (net (code "75") (name "Net-(U4-4B)") (class "Default")
      (node (ref "R24") (pin "1") (pinfunction "1_1") (pintype "passive"))
      (node (ref "U4") (pin "4") (pinfunction "4B_4") (pintype "passive"))
    )
    (net (code "76") (name "Net-(U5-LX)") (class "Default")
      (node (ref "L4") (pin "2") (pinfunction "2_2") (pintype "passive"))
      (node (ref "U5") (pin "2") (pinfunction "LX_2") (pintype "passive"))
    )
    (net (code "77") (name "Net-(U6-1B)") (class "Default")
      (node (ref "R25") (pin "1") (pinfunction "1_1") (pintype "passive"))
      (node (ref "U6") (pin "1") (pinfunction "1B_1") (pintype "passive"))
    )
    (net (code "78") (name "Net-(U6-2B)") (class "Default")
      (node (ref "R26") (pin "1") (pinfunction "1_1") (pintype "passive"))
      (node (ref "U6") (pin "2") (pinfunction "2B_2") (pintype "passive"))
    )
    (net (code "79") (name "Net-(U6-3B)") (class "Default")
      (node (ref "R27") (pin "1") (pinfunction "1_1") (pintype "passive"))
      (node (ref "U6") (pin "3") (pinfunction "3B_3") (pintype "passive"))
    )
    (net (code "80") (name "Net-(U6-4B)") (class "Default")
      (node (ref "R28") (pin "1") (pinfunction "1_1") (pintype "passive"))
      (node (ref "U6") (pin "4") (pinfunction "4B_4") (pintype "passive"))
    )
    (net (code "81") (name "VCC_USB") (class "Default")
      (node (ref "C1") (pin "2") (pinfunction "2_2") (pintype "passive"))
      (node (ref "D1") (pin "2") (pinfunction "2_2") (pintype "passive"))
      (node (ref "D7") (pin "1") (pinfunction "A_1") (pintype "passive"))
      (node (ref "Q6") (pin "1") (pinfunction "G_1") (pintype "passive"))
      (node (ref "R3") (pin "2") (pinfunction "2_2") (pintype "passive"))
      (node (ref "R35") (pin "1") (pinfunction "1_1") (pintype "passive"))
      (node (ref "R37") (pin "2") (pinfunction "2_2") (pintype "passive"))
      (node (ref "USB1") (pin "A9") (pinfunction "VBUS_A9") (pintype "passive"))
      (node (ref "USB1") (pin "B9") (pinfunction "VBUS_B9") (pintype "passive"))
    )
    (net (code "82") (name "unconnected-(BAT1-Pad4)") (class "Default")
      (node (ref "BAT1") (pin "4") (pinfunction "4_4") (pintype "passive"))
    )
    (net (code "83") (name "unconnected-(BAT1-Pad5)") (class "Default")
      (node (ref "BAT1") (pin "5") (pinfunction "5_5") (pintype "passive"))
    )
    (net (code "84") (name "unconnected-(CN1-Pad3)") (class "Default")
      (node (ref "CN1") (pin "3") (pinfunction "3_3") (pintype "passive"))
    )
    (net (code "85") (name "unconnected-(CN1-Pad4)") (class "Default")
      (node (ref "CN1") (pin "4") (pinfunction "4_4") (pintype "passive"))
    )
    (net (code "86") (name "unconnected-(CN2-Pad5)") (class "Default")
      (node (ref "CN2") (pin "5") (pinfunction "5_5") (pintype "passive"))
    )
    (net (code "87") (name "unconnected-(CN2-Pad6)") (class "Default")
      (node (ref "CN2") (pin "6") (pinfunction "6_6") (pintype "passive"))
    )
    (net (code "88") (name "unconnected-(J1-Pad6)") (class "Default")
      (node (ref "J1") (pin "6") (pinfunction "6_6") (pintype "passive"))
    )
    (net (code "89") (name "unconnected-(J1-Pad7)") (class "Default")
      (node (ref "J1") (pin "7") (pinfunction "7_7") (pintype "passive"))
    )
    (net (code "90") (name "unconnected-(J2-Pad6)") (class "Default")
      (node (ref "J2") (pin "6") (pinfunction "6_6") (pintype "passive"))
    )
    (net (code "91") (name "unconnected-(J2-Pad7)") (class "Default")
      (node (ref "J2") (pin "7") (pinfunction "7_7") (pintype "passive"))
    )
    (net (code "92") (name "unconnected-(P1-Pad1)") (class "Default")
      (node (ref "P1") (pin "1") (pinfunction "1_1") (pintype "passive"))
    )
    (net (code "93") (name "unconnected-(U1-STDBY-Pad6)") (class "Default")
      (node (ref "U1") (pin "6") (pinfunction "STDBY_6") (pintype "passive"))
    )
    (net (code "94") (name "unconnected-(U2-NC-Pad4)") (class "Default")
      (node (ref "U2") (pin "4") (pinfunction "NC_4") (pintype "passive"))
    )
    (net (code "95") (name "unconnected-(U3-PC[7]-Pad33)") (class "Default")
      (node (ref "U3") (pin "33") (pinfunction "PC[7]_33") (pintype "passive"))
    )
    (net (code "96") (name "unconnected-(U3-PD[0]-Pad36)") (class "Default")
      (node (ref "U3") (pin "36") (pinfunction "PD[0]_36") (pintype "passive"))
    )
    (net (code "97") (name "unconnected-(U3-PD[1]-Pad37)") (class "Default")
      (node (ref "U3") (pin "37") (pinfunction "PD[1]_37") (pintype "passive"))
    )
    (net (code "98") (name "unconnected-(U3-PD[4]-Pad40)") (class "Default")
      (node (ref "U3") (pin "40") (pinfunction "PD[4]_40") (pintype "passive"))
    )
    (net (code "99") (name "unconnected-(U3-PF[1]-Pad35)") (class "Default")
      (node (ref "U3") (pin "35") (pinfunction "PF[1]_35") (pintype "passive"))
    )
  )
)
